# amp_test_arm.net
KiCad netlist of a schematic drawn in EAGLE
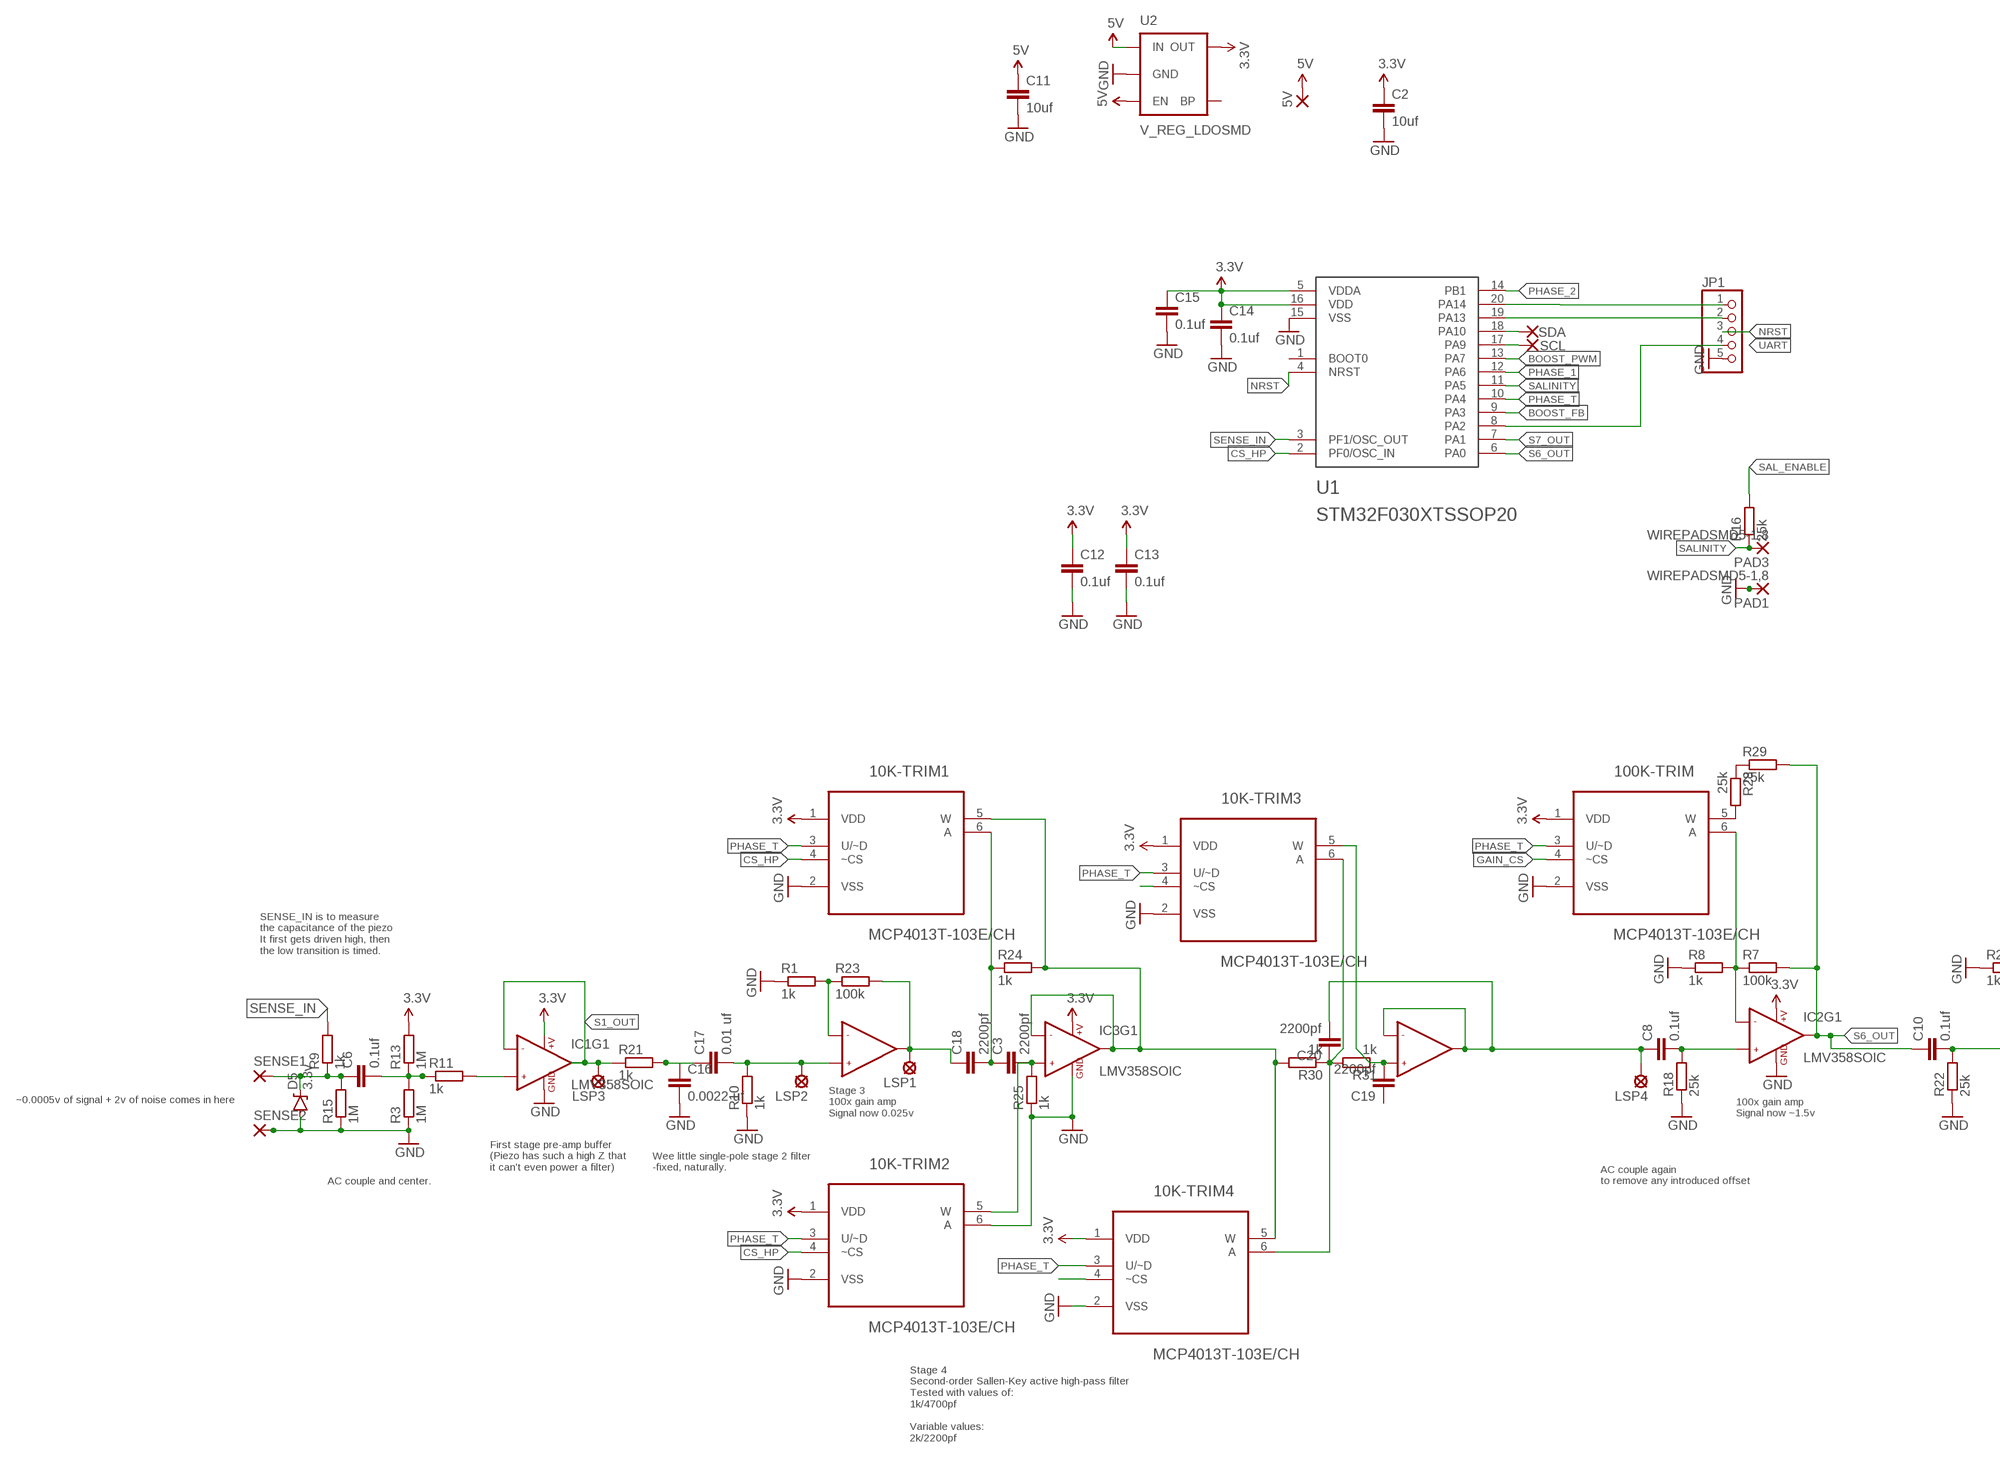
[diagram p0: schematic, sheet 1, part 1 of 2]
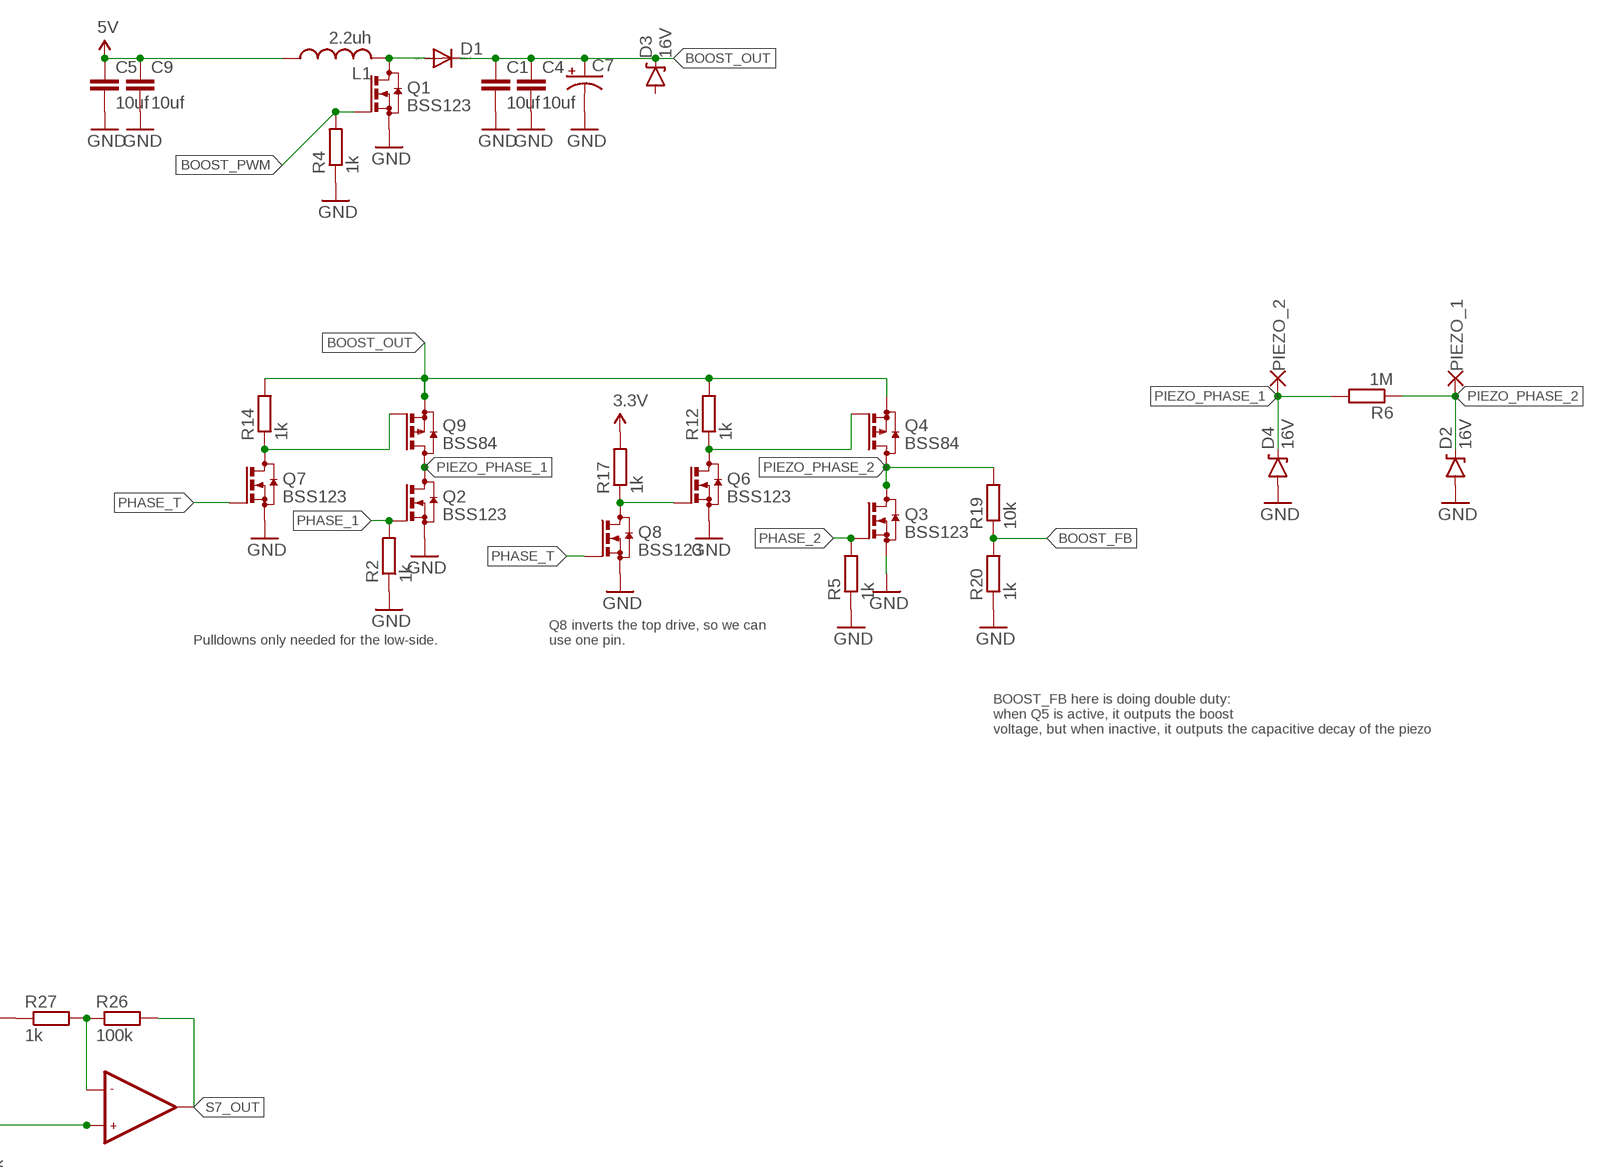
[diagram p1: schematic, sheet 1, part 2 of 2]

(export (version "E")
  (design (tool "Eeschema 10.0.6"))
  (components
    (comp (ref "5V")
      (value "SMD5")
      (footprint "eagle-import:SMD2,54-5,08")
      (libsource (lib "eagle-import") (part "SMD5"))
    )
    (comp (ref "10K-TRIM1")
      (value "MCP4013T-103E/CH")
      (footprint "eagle-import:SOT95P280X145-6N")
      (fields (field (name "DIGI-KEY_PART_NUMBER") "MCP4013T-103E/CHCT-ND") (field (name "MF") "Microchip"))
      (libsource (lib "eagle-import") (part "MCP4013T-103E/CH"))
    )
    (comp (ref "10K-TRIM2")
      (value "MCP4013T-103E/CH")
      (footprint "eagle-import:SOT95P280X145-6N")
      (fields (field (name "DIGI-KEY_PART_NUMBER") "MCP4013T-103E/CHCT-ND") (field (name "MF") "Microchip"))
      (libsource (lib "eagle-import") (part "MCP4013T-103E/CH"))
    )
    (comp (ref "10K-TRIM3")
      (value "MCP4013T-103E/CH")
      (footprint "eagle-import:SOT95P280X145-6N")
      (fields (field (name "DIGI-KEY_PART_NUMBER") "MCP4013T-103E/CHCT-ND") (field (name "MF") "Microchip"))
      (libsource (lib "eagle-import") (part "MCP4013T-103E/CH"))
    )
    (comp (ref "10K-TRIM4")
      (value "MCP4013T-103E/CH")
      (footprint "eagle-import:SOT95P280X145-6N")
      (fields (field (name "DIGI-KEY_PART_NUMBER") "MCP4013T-103E/CHCT-ND") (field (name "MF") "Microchip"))
      (libsource (lib "eagle-import") (part "MCP4013T-103E/CH"))
    )
    (comp (ref "100K-TRIM")
      (value "MCP4013T-103E/CH")
      (footprint "eagle-import:SOT95P280X145-6N")
      (fields (field (name "DIGI-KEY_PART_NUMBER") "MCP4013T-103E/CHCT-ND") (field (name "MF") "Microchip"))
      (libsource (lib "eagle-import") (part "MCP4013T-103E/CH"))
    )
    (comp (ref "C1")
      (value "10uf")
      (footprint "eagle-import:C0805")
      (libsource (lib "eagle-import") (part "C-EUC0805"))
    )
    (comp (ref "C2")
      (value "10uf")
      (footprint "eagle-import:C0603")
      (libsource (lib "eagle-import") (part "C-EUC0603"))
    )
    (comp (ref "C3")
      (value "2200pf")
      (footprint "eagle-import:C0603")
      (libsource (lib "eagle-import") (part "C-EUC0603"))
    )
    (comp (ref "C4")
      (value "10uf")
      (footprint "eagle-import:C0805")
      (libsource (lib "eagle-import") (part "C-EUC0805"))
    )
    (comp (ref "C5")
      (value "10uf")
      (footprint "eagle-import:C0603")
      (libsource (lib "eagle-import") (part "C-EUC0603"))
    )
    (comp (ref "C6")
      (value "0.1uf")
      (footprint "eagle-import:C0603")
      (libsource (lib "eagle-import") (part "C-EUC0603"))
    )
    (comp (ref "C7")
      (value "CAP_POLPTH1")
      (footprint "eagle-import:CPOL-RADIAL-100UF-25V")
      (libsource (lib "eagle-import") (part "CAP_POLPTH1"))
    )
    (comp (ref "C8")
      (value "0.1uf")
      (footprint "eagle-import:C0603")
      (libsource (lib "eagle-import") (part "C-EUC0603"))
    )
    (comp (ref "C9")
      (value "10uf")
      (footprint "eagle-import:C0603")
      (libsource (lib "eagle-import") (part "C-EUC0603"))
    )
    (comp (ref "C10")
      (value "0.1uf")
      (footprint "eagle-import:C0603")
      (libsource (lib "eagle-import") (part "C-EUC0603"))
    )
    (comp (ref "C11")
      (value "10uf")
      (footprint "eagle-import:C0603")
      (libsource (lib "eagle-import") (part "C-EUC0603"))
    )
    (comp (ref "C12")
      (value "0.1uf")
      (footprint "eagle-import:C0603")
      (libsource (lib "eagle-import") (part "C-EUC0603"))
    )
    (comp (ref "C13")
      (value "0.1uf")
      (footprint "eagle-import:C0603")
      (libsource (lib "eagle-import") (part "C-EUC0603"))
    )
    (comp (ref "C14")
      (value "0.1uf")
      (footprint "eagle-import:C0603")
      (libsource (lib "eagle-import") (part "C-EUC0603"))
    )
    (comp (ref "C15")
      (value "0.1uf")
      (footprint "eagle-import:C0603")
      (libsource (lib "eagle-import") (part "C-EUC0603"))
    )
    (comp (ref "C16")
      (value "0.0022 uf")
      (footprint "eagle-import:C0603")
      (libsource (lib "eagle-import") (part "C-EUC0603"))
    )
    (comp (ref "C17")
      (value "0.01 uf")
      (footprint "eagle-import:C0603")
      (libsource (lib "eagle-import") (part "C-EUC0603"))
    )
    (comp (ref "C18")
      (value "2200pf")
      (footprint "eagle-import:C0603")
      (libsource (lib "eagle-import") (part "C-EUC0603"))
    )
    (comp (ref "C19")
      (value "2200pf")
      (footprint "eagle-import:C0603")
      (libsource (lib "eagle-import") (part "C-EUC0603"))
    )
    (comp (ref "C20")
      (value "2200pf")
      (footprint "eagle-import:C0603")
      (libsource (lib "eagle-import") (part "C-EUC0603"))
    )
    (comp (ref "D1")
      (value "CGRM4001-G")
      (footprint "eagle-import:SOD-123_MINI-SMA")
      (libsource (lib "eagle-import") (part "CGRM400-G1"))
    )
    (comp (ref "D2")
      (value "16V")
      (footprint "eagle-import:SOD-323")
      (libsource (lib "eagle-import") (part "DIODE-ZENER3.3V"))
    )
    (comp (ref "D3")
      (value "16V")
      (footprint "eagle-import:SOD-323")
      (libsource (lib "eagle-import") (part "DIODE-ZENER3.3V"))
    )
    (comp (ref "D4")
      (value "16V")
      (footprint "eagle-import:SOD-323")
      (libsource (lib "eagle-import") (part "DIODE-ZENER3.3V"))
    )
    (comp (ref "D5")
      (value "3.3v")
      (footprint "eagle-import:SOD-323")
      (libsource (lib "eagle-import") (part "DIODE-ZENER3.3V"))
    )
    (comp (ref "IC1")
      (value "LMV358SOIC")
      (footprint "eagle-import:SO08")
      (libsource (lib "eagle-import") (part "LMV358SOIC"))
    )
    (comp (ref "IC2")
      (value "LMV358SOIC")
      (footprint "eagle-import:SO08")
      (libsource (lib "eagle-import") (part "LMV358SOIC"))
    )
    (comp (ref "IC3")
      (value "LMV358SOIC")
      (footprint "eagle-import:SO08")
      (libsource (lib "eagle-import") (part "LMV358SOIC"))
    )
    (comp (ref "JP1")
      (value "PINHD-1X5")
      (footprint "eagle-import:1X05")
      (libsource (lib "eagle-import") (part "PINHD-1X5"))
    )
    (comp (ref "L1")
      (value "2.2uh")
      (footprint "eagle-import:L2825P")
      (libsource (lib "eagle-import") (part "L-USL2825P"))
    )
    (comp (ref "LSP1")
      (value "LSP10")
      (footprint "eagle-import:LSP10")
      (libsource (lib "eagle-import") (part "LSP10"))
    )
    (comp (ref "LSP2")
      (value "LSP10")
      (footprint "eagle-import:LSP10")
      (libsource (lib "eagle-import") (part "LSP10"))
    )
    (comp (ref "LSP3")
      (value "LSP10")
      (footprint "eagle-import:LSP10")
      (libsource (lib "eagle-import") (part "LSP10"))
    )
    (comp (ref "LSP4")
      (value "LSP10")
      (footprint "eagle-import:LSP10")
      (libsource (lib "eagle-import") (part "LSP10"))
    )
    (comp (ref "PAD1")
      (value "WIREPADSMD5-1,8")
      (footprint "eagle-import:5-1,8")
      (libsource (lib "eagle-import") (part "WIREPADSMD5-1,8"))
    )
    (comp (ref "PAD3")
      (value "WIREPADSMD5-1,8")
      (footprint "eagle-import:5-1,8")
      (libsource (lib "eagle-import") (part "WIREPADSMD5-1,8"))
    )
    (comp (ref "PIEZO_1")
      (value "SMD5")
      (footprint "eagle-import:SMD2,54-5,08")
      (libsource (lib "eagle-import") (part "SMD5"))
    )
    (comp (ref "PIEZO_2")
      (value "SMD5")
      (footprint "eagle-import:SMD2,54-5,08")
      (libsource (lib "eagle-import") (part "SMD5"))
    )
    (comp (ref "Q1")
      (value "BSS123")
      (footprint "eagle-import:SOT23")
      (libsource (lib "eagle-import") (part "BSS123"))
    )
    (comp (ref "Q2")
      (value "BSS123")
      (footprint "eagle-import:SOT23")
      (libsource (lib "eagle-import") (part "BSS123"))
    )
    (comp (ref "Q3")
      (value "BSS123")
      (footprint "eagle-import:SOT23")
      (libsource (lib "eagle-import") (part "BSS123"))
    )
    (comp (ref "Q4")
      (value "BSS84")
      (footprint "eagle-import:SOT23")
      (libsource (lib "eagle-import") (part "BSS84"))
    )
    (comp (ref "Q6")
      (value "BSS123")
      (footprint "eagle-import:SOT23")
      (libsource (lib "eagle-import") (part "BSS123"))
    )
    (comp (ref "Q7")
      (value "BSS123")
      (footprint "eagle-import:SOT23")
      (libsource (lib "eagle-import") (part "BSS123"))
    )
    (comp (ref "Q8")
      (value "BSS123")
      (footprint "eagle-import:SOT23")
      (libsource (lib "eagle-import") (part "BSS123"))
    )
    (comp (ref "Q9")
      (value "BSS84")
      (footprint "eagle-import:SOT23")
      (libsource (lib "eagle-import") (part "BSS84"))
    )
    (comp (ref "R1")
      (value "1k")
      (footprint "eagle-import:R0603")
      (libsource (lib "eagle-import") (part "R-EU_R0603"))
    )
    (comp (ref "R2")
      (value "1k")
      (footprint "eagle-import:R0603")
      (libsource (lib "eagle-import") (part "R-EU_R0603"))
    )
    (comp (ref "R3")
      (value "1M")
      (footprint "eagle-import:R0603")
      (libsource (lib "eagle-import") (part "R-EU_R0603"))
    )
    (comp (ref "R4")
      (value "1k")
      (footprint "eagle-import:R0603")
      (libsource (lib "eagle-import") (part "R-EU_R0603"))
    )
    (comp (ref "R5")
      (value "1k")
      (footprint "eagle-import:R0603")
      (libsource (lib "eagle-import") (part "R-EU_R0603"))
    )
    (comp (ref "R6")
      (value "1M")
      (footprint "eagle-import:R0603")
      (libsource (lib "eagle-import") (part "R-EU_R0603"))
    )
    (comp (ref "R7")
      (value "100k")
      (footprint "eagle-import:R0603")
      (libsource (lib "eagle-import") (part "R-EU_R0603"))
    )
    (comp (ref "R8")
      (value "1k")
      (footprint "eagle-import:R0603")
      (libsource (lib "eagle-import") (part "R-EU_R0603"))
    )
    (comp (ref "R9")
      (value "1k")
      (footprint "eagle-import:R0603")
      (libsource (lib "eagle-import") (part "R-EU_R0603"))
    )
    (comp (ref "R10")
      (value "1k")
      (footprint "eagle-import:R0603")
      (libsource (lib "eagle-import") (part "R-EU_R0603"))
    )
    (comp (ref "R11")
      (value "1k")
      (footprint "eagle-import:R0603")
      (libsource (lib "eagle-import") (part "R-EU_R0603"))
    )
    (comp (ref "R12")
      (value "1k")
      (footprint "eagle-import:R0603")
      (libsource (lib "eagle-import") (part "R-EU_R0603"))
    )
    (comp (ref "R13")
      (value "1M")
      (footprint "eagle-import:R0603")
      (libsource (lib "eagle-import") (part "R-EU_R0603"))
    )
    (comp (ref "R14")
      (value "1k")
      (footprint "eagle-import:R0603")
      (libsource (lib "eagle-import") (part "R-EU_R0603"))
    )
    (comp (ref "R15")
      (value "1M")
      (footprint "eagle-import:R0603")
      (libsource (lib "eagle-import") (part "R-EU_R0603"))
    )
    (comp (ref "R16")
      (value "25k")
      (footprint "eagle-import:R0603")
      (libsource (lib "eagle-import") (part "R-EU_R0603"))
    )
    (comp (ref "R17")
      (value "1k")
      (footprint "eagle-import:R0603")
      (libsource (lib "eagle-import") (part "R-EU_R0603"))
    )
    (comp (ref "R18")
      (value "25k")
      (footprint "eagle-import:R0603")
      (libsource (lib "eagle-import") (part "R-EU_R0603"))
    )
    (comp (ref "R19")
      (value "10k")
      (footprint "eagle-import:R0603")
      (libsource (lib "eagle-import") (part "R-EU_R0603"))
    )
    (comp (ref "R20")
      (value "1k")
      (footprint "eagle-import:R0603")
      (libsource (lib "eagle-import") (part "R-EU_R0603"))
    )
    (comp (ref "R21")
      (value "1k")
      (footprint "eagle-import:R0603")
      (libsource (lib "eagle-import") (part "R-EU_R0603"))
    )
    (comp (ref "R22")
      (value "25k")
      (footprint "eagle-import:R0603")
      (libsource (lib "eagle-import") (part "R-EU_R0603"))
    )
    (comp (ref "R23")
      (value "100k")
      (footprint "eagle-import:R0603")
      (libsource (lib "eagle-import") (part "R-EU_R0603"))
    )
    (comp (ref "R24")
      (value "1k")
      (footprint "eagle-import:R0603")
      (libsource (lib "eagle-import") (part "R-EU_R0603"))
    )
    (comp (ref "R25")
      (value "1k")
      (footprint "eagle-import:R0603")
      (libsource (lib "eagle-import") (part "R-EU_R0603"))
    )
    (comp (ref "R26")
      (value "100k")
      (footprint "eagle-import:R0603")
      (libsource (lib "eagle-import") (part "R-EU_R0603"))
    )
    (comp (ref "R27")
      (value "1k")
      (footprint "eagle-import:R0603")
      (libsource (lib "eagle-import") (part "R-EU_R0603"))
    )
    (comp (ref "R28")
      (value "25k")
      (footprint "eagle-import:R0603")
      (libsource (lib "eagle-import") (part "R-EU_R0603"))
    )
    (comp (ref "R29")
      (value "25k")
      (footprint "eagle-import:R0603")
      (libsource (lib "eagle-import") (part "R-EU_R0603"))
    )
    (comp (ref "R30")
      (value "1k")
      (footprint "eagle-import:R0603")
      (libsource (lib "eagle-import") (part "R-EU_R0603"))
    )
    (comp (ref "R31")
      (value "1k")
      (footprint "eagle-import:R0603")
      (libsource (lib "eagle-import") (part "R-EU_R0603"))
    )
    (comp (ref "SCL")
      (value "SMD5")
      (footprint "eagle-import:SMD2,54-5,08")
      (libsource (lib "eagle-import") (part "SMD5"))
    )
    (comp (ref "SDA")
      (value "SMD5")
      (footprint "eagle-import:SMD2,54-5,08")
      (libsource (lib "eagle-import") (part "SMD5"))
    )
    (comp (ref "SENSE1")
      (value "SMD5")
      (footprint "eagle-import:SMD2,54-5,08")
      (libsource (lib "eagle-import") (part "SMD5"))
    )
    (comp (ref "SENSE2")
      (value "SMD5")
      (footprint "eagle-import:SMD2,54-5,08")
      (libsource (lib "eagle-import") (part "SMD5"))
    )
    (comp (ref "U1")
      (value "STM32F030XTSSOP20")
      (footprint "eagle-import:TSSOP-20")
      (libsource (lib "eagle-import") (part "STM32F030XTSSOP20"))
    )
    (comp (ref "U2")
      (value "V_REG_LDOSMD")
      (footprint "eagle-import:SOT23-5")
      (libsource (lib "eagle-import") (part "V_REG_LDOSMD"))
    )
  )
  (nets
    (net (code "1") (name "3.3V") (class "Default")
      (node (ref "100K-TRIM") (pin "1") (pinfunction "VDD_1") (pintype "power_in"))
      (node (ref "10K-TRIM1") (pin "1") (pinfunction "VDD_1") (pintype "power_in"))
      (node (ref "10K-TRIM2") (pin "1") (pinfunction "VDD_1") (pintype "power_in"))
      (node (ref "10K-TRIM3") (pin "1") (pinfunction "VDD_1") (pintype "power_in"))
      (node (ref "10K-TRIM4") (pin "1") (pinfunction "VDD_1") (pintype "power_in"))
      (node (ref "C12") (pin "1") (pinfunction "1_1") (pintype "passive"))
      (node (ref "C13") (pin "1") (pinfunction "1_1") (pintype "passive"))
      (node (ref "C14") (pin "1") (pinfunction "1_1") (pintype "passive"))
      (node (ref "C15") (pin "1") (pinfunction "1_1") (pintype "passive"))
      (node (ref "C2") (pin "1") (pinfunction "1_1") (pintype "passive"))
      (node (ref "IC1") (pin "8") (pinfunction "+V_8") (pintype "power_in"))
      (node (ref "IC2") (pin "8") (pinfunction "+V_8") (pintype "power_in"))
      (node (ref "IC3") (pin "8") (pinfunction "+V_8") (pintype "power_in"))
      (node (ref "R13") (pin "2") (pinfunction "2_2") (pintype "passive"))
      (node (ref "R17") (pin "2") (pinfunction "2_2") (pintype "passive"))
      (node (ref "U1") (pin "16") (pinfunction "VDD_16") (pintype "bidirectional"))
      (node (ref "U1") (pin "5") (pinfunction "VDDA_5") (pintype "bidirectional"))
      (node (ref "U2") (pin "5") (pinfunction "OUT_5") (pintype "passive"))
    )
    (net (code "2") (name "5V") (class "Default")
      (node (ref "5V") (pin "1") (pinfunction "P_1") (pintype "passive"))
      (node (ref "C11") (pin "1") (pinfunction "1_1") (pintype "passive"))
      (node (ref "C5") (pin "1") (pinfunction "1_1") (pintype "passive"))
      (node (ref "C9") (pin "1") (pinfunction "1_1") (pintype "passive"))
      (node (ref "L1") (pin "1") (pinfunction "1_1") (pintype "passive"))
      (node (ref "U2") (pin "1") (pinfunction "IN_1") (pintype "input"))
      (node (ref "U2") (pin "3") (pinfunction "EN_3") (pintype "input"))
    )
    (net (code "3") (name "BOOST_FB") (class "Default")
      (node (ref "R19") (pin "1") (pinfunction "1_1") (pintype "passive"))
      (node (ref "R20") (pin "2") (pinfunction "2_2") (pintype "passive"))
      (node (ref "U1") (pin "9") (pinfunction "PA3_9") (pintype "bidirectional"))
    )
    (net (code "4") (name "BOOST_OUT") (class "Default")
      (node (ref "C1") (pin "1") (pinfunction "1_1") (pintype "passive"))
      (node (ref "C4") (pin "1") (pinfunction "1_1") (pintype "passive"))
      (node (ref "C7") (pin "1") (pinfunction "+_1") (pintype "passive"))
      (node (ref "D1") (pin "C") (pinfunction "C_C") (pintype "passive"))
      (node (ref "D3") (pin "C") (pinfunction "C_C") (pintype "passive"))
      (node (ref "Q4") (pin "2") (pinfunction "S_2") (pintype "passive"))
      (node (ref "Q9") (pin "2") (pinfunction "S_2") (pintype "passive"))
      (node (ref "R12") (pin "2") (pinfunction "2_2") (pintype "passive"))
      (node (ref "R14") (pin "2") (pinfunction "2_2") (pintype "passive"))
    )
    (net (code "5") (name "BOOST_PWM") (class "Default")
      (node (ref "Q1") (pin "1") (pinfunction "G_1") (pintype "passive"))
      (node (ref "R4") (pin "2") (pinfunction "2_2") (pintype "passive"))
      (node (ref "U1") (pin "13") (pinfunction "PA7_13") (pintype "bidirectional"))
    )
    (net (code "6") (name "CS_HP") (class "Default")
      (node (ref "10K-TRIM1") (pin "4") (pinfunction "~{CS}_4") (pintype "input"))
      (node (ref "10K-TRIM2") (pin "4") (pinfunction "~{CS}_4") (pintype "input"))
      (node (ref "U1") (pin "2") (pinfunction "PF0/OSC_IN_2") (pintype "bidirectional"))
    )
    (net (code "7") (name "GAIN_CS") (class "Default")
      (node (ref "100K-TRIM") (pin "4") (pinfunction "~{CS}_4") (pintype "input"))
    )
    (net (code "8") (name "GND") (class "Default")
      (node (ref "100K-TRIM") (pin "2") (pinfunction "VSS_2") (pintype "power_in"))
      (node (ref "10K-TRIM1") (pin "2") (pinfunction "VSS_2") (pintype "power_in"))
      (node (ref "10K-TRIM2") (pin "2") (pinfunction "VSS_2") (pintype "power_in"))
      (node (ref "10K-TRIM2") (pin "6") (pinfunction "A_6") (pintype "passive"))
      (node (ref "10K-TRIM3") (pin "2") (pinfunction "VSS_2") (pintype "power_in"))
      (node (ref "10K-TRIM4") (pin "2") (pinfunction "VSS_2") (pintype "power_in"))
      (node (ref "C1") (pin "2") (pinfunction "2_2") (pintype "passive"))
      (node (ref "C11") (pin "2") (pinfunction "2_2") (pintype "passive"))
      (node (ref "C12") (pin "2") (pinfunction "2_2") (pintype "passive"))
      (node (ref "C13") (pin "2") (pinfunction "2_2") (pintype "passive"))
      (node (ref "C14") (pin "2") (pinfunction "2_2") (pintype "passive"))
      (node (ref "C15") (pin "2") (pinfunction "2_2") (pintype "passive"))
      (node (ref "C16") (pin "2") (pinfunction "2_2") (pintype "passive"))
      (node (ref "C2") (pin "2") (pinfunction "2_2") (pintype "passive"))
      (node (ref "C4") (pin "2") (pinfunction "2_2") (pintype "passive"))
      (node (ref "C5") (pin "2") (pinfunction "2_2") (pintype "passive"))
      (node (ref "C7") (pin "2") (pinfunction "-_2") (pintype "passive"))
      (node (ref "C9") (pin "2") (pinfunction "2_2") (pintype "passive"))
      (node (ref "D2") (pin "A") (pinfunction "A_A") (pintype "passive"))
      (node (ref "D4") (pin "A") (pinfunction "A_A") (pintype "passive"))
      (node (ref "D5") (pin "A") (pinfunction "A_A") (pintype "passive"))
      (node (ref "IC1") (pin "4") (pinfunction "GND_4") (pintype "power_in"))
      (node (ref "IC2") (pin "4") (pinfunction "GND_4") (pintype "power_in"))
      (node (ref "IC3") (pin "4") (pinfunction "GND_4") (pintype "power_in"))
      (node (ref "JP1") (pin "5") (pinfunction "5_5") (pintype "passive"))
      (node (ref "PAD1") (pin "1") (pinfunction "P_1") (pintype "passive"))
      (node (ref "Q1") (pin "2") (pinfunction "S_2") (pintype "passive"))
      (node (ref "Q2") (pin "2") (pinfunction "S_2") (pintype "passive"))
      (node (ref "Q3") (pin "2") (pinfunction "S_2") (pintype "passive"))
      (node (ref "Q6") (pin "2") (pinfunction "S_2") (pintype "passive"))
      (node (ref "Q7") (pin "2") (pinfunction "S_2") (pintype "passive"))
      (node (ref "Q8") (pin "2") (pinfunction "S_2") (pintype "passive"))
      (node (ref "R1") (pin "1") (pinfunction "1_1") (pintype "passive"))
      (node (ref "R10") (pin "1") (pinfunction "1_1") (pintype "passive"))
      (node (ref "R15") (pin "1") (pinfunction "1_1") (pintype "passive"))
      (node (ref "R18") (pin "1") (pinfunction "1_1") (pintype "passive"))
      (node (ref "R2") (pin "1") (pinfunction "1_1") (pintype "passive"))
      (node (ref "R20") (pin "1") (pinfunction "1_1") (pintype "passive"))
      (node (ref "R22") (pin "1") (pinfunction "1_1") (pintype "passive"))
      (node (ref "R25") (pin "1") (pinfunction "1_1") (pintype "passive"))
      (node (ref "R27") (pin "1") (pinfunction "1_1") (pintype "passive"))
      (node (ref "R3") (pin "1") (pinfunction "1_1") (pintype "passive"))
      (node (ref "R4") (pin "1") (pinfunction "1_1") (pintype "passive"))
      (node (ref "R5") (pin "1") (pinfunction "1_1") (pintype "passive"))
      (node (ref "R8") (pin "1") (pinfunction "1_1") (pintype "passive"))
      (node (ref "SENSE2") (pin "1") (pinfunction "P_1") (pintype "passive"))
      (node (ref "U1") (pin "15") (pinfunction "VSS_15") (pintype "bidirectional"))
      (node (ref "U2") (pin "2") (pinfunction "GND_2") (pintype "input"))
    )
    (net (code "9") (name "NRST") (class "Default")
      (node (ref "JP1") (pin "3") (pinfunction "3_3") (pintype "passive"))
      (node (ref "U1") (pin "4") (pinfunction "NRST_4") (pintype "bidirectional"))
    )
    (net (code "10") (name "Net-(10K-TRIM1-A)") (class "Default")
      (node (ref "10K-TRIM1") (pin "6") (pinfunction "A_6") (pintype "passive"))
      (node (ref "C18") (pin "2") (pinfunction "2_2") (pintype "passive"))
      (node (ref "C3") (pin "1") (pinfunction "1_1") (pintype "passive"))
      (node (ref "R24") (pin "1") (pinfunction "1_1") (pintype "passive"))
    )
    (net (code "11") (name "Net-(10K-TRIM1-W)") (class "Default")
      (node (ref "10K-TRIM1") (pin "5") (pinfunction "W_5") (pintype "passive"))
      (node (ref "10K-TRIM4") (pin "5") (pinfunction "W_5") (pintype "passive"))
      (node (ref "IC3") (pin "1") (pinfunction "OUT1_1") (pintype "output"))
      (node (ref "IC3") (pin "2") (pinfunction "-IN1_2") (pintype "input"))
      (node (ref "R24") (pin "2") (pinfunction "2_2") (pintype "passive"))
      (node (ref "R30") (pin "2") (pinfunction "2_2") (pintype "passive"))
    )
    (net (code "12") (name "Net-(10K-TRIM2-W)") (class "Default")
      (node (ref "10K-TRIM2") (pin "5") (pinfunction "W_5") (pintype "passive"))
      (node (ref "C3") (pin "2") (pinfunction "2_2") (pintype "passive"))
      (node (ref "IC3") (pin "3") (pinfunction "+IN1_3") (pintype "input"))
      (node (ref "R25") (pin "2") (pinfunction "2_2") (pintype "passive"))
    )
    (net (code "13") (name "Net-(10K-TRIM3-A)") (class "Default")
      (node (ref "10K-TRIM3") (pin "6") (pinfunction "A_6") (pintype "passive"))
      (node (ref "10K-TRIM4") (pin "6") (pinfunction "A_6") (pintype "passive"))
      (node (ref "C20") (pin "1") (pinfunction "1_1") (pintype "passive"))
      (node (ref "R30") (pin "1") (pinfunction "1_1") (pintype "passive"))
      (node (ref "R31") (pin "2") (pinfunction "2_2") (pintype "passive"))
    )
    (net (code "14") (name "Net-(10K-TRIM3-W)") (class "Default")
      (node (ref "10K-TRIM3") (pin "5") (pinfunction "W_5") (pintype "passive"))
      (node (ref "C19") (pin "2") (pinfunction "2_2") (pintype "passive"))
      (node (ref "IC3") (pin "5") (pinfunction "+IN2_5") (pintype "input"))
      (node (ref "R31") (pin "1") (pinfunction "1_1") (pintype "passive"))
    )
    (net (code "15") (name "Net-(100K-TRIM-A)") (class "Default")
      (node (ref "100K-TRIM") (pin "6") (pinfunction "A_6") (pintype "passive"))
      (node (ref "IC2") (pin "2") (pinfunction "-IN1_2") (pintype "input"))
      (node (ref "R7") (pin "1") (pinfunction "1_1") (pintype "passive"))
      (node (ref "R8") (pin "2") (pinfunction "2_2") (pintype "passive"))
    )
    (net (code "16") (name "Net-(100K-TRIM-W)") (class "Default")
      (node (ref "100K-TRIM") (pin "5") (pinfunction "W_5") (pintype "passive"))
      (node (ref "R28") (pin "2") (pinfunction "2_2") (pintype "passive"))
    )
    (net (code "17") (name "Net-(C6-Pad2)") (class "Default")
      (node (ref "C6") (pin "2") (pinfunction "2_2") (pintype "passive"))
      (node (ref "R11") (pin "1") (pinfunction "1_1") (pintype "passive"))
      (node (ref "R13") (pin "1") (pinfunction "1_1") (pintype "passive"))
      (node (ref "R3") (pin "2") (pinfunction "2_2") (pintype "passive"))
    )
    (net (code "18") (name "Net-(C16-Pad1)") (class "Default")
      (node (ref "C16") (pin "1") (pinfunction "1_1") (pintype "passive"))
      (node (ref "C17") (pin "1") (pinfunction "1_1") (pintype "passive"))
      (node (ref "R21") (pin "2") (pinfunction "2_2") (pintype "passive"))
    )
    (net (code "19") (name "Net-(IC1A-+IN1)") (class "Default")
      (node (ref "IC1") (pin "3") (pinfunction "+IN1_3") (pintype "input"))
      (node (ref "R11") (pin "2") (pinfunction "2_2") (pintype "passive"))
    )
    (net (code "20") (name "Net-(IC1B-+IN2)") (class "Default")
      (node (ref "C17") (pin "2") (pinfunction "2_2") (pintype "passive"))
      (node (ref "IC1") (pin "5") (pinfunction "+IN2_5") (pintype "input"))
      (node (ref "LSP2") (pin "MP") (pinfunction "MP_MP") (pintype "passive"))
      (node (ref "R10") (pin "2") (pinfunction "2_2") (pintype "passive"))
    )
    (net (code "21") (name "Net-(IC1B--IN2)") (class "Default")
      (node (ref "IC1") (pin "6") (pinfunction "-IN2_6") (pintype "input"))
      (node (ref "R1") (pin "2") (pinfunction "2_2") (pintype "passive"))
      (node (ref "R23") (pin "1") (pinfunction "1_1") (pintype "passive"))
    )
    (net (code "22") (name "Net-(IC1B-OUT2)") (class "Default")
      (node (ref "C18") (pin "1") (pinfunction "1_1") (pintype "passive"))
      (node (ref "IC1") (pin "7") (pinfunction "OUT2_7") (pintype "output"))
      (node (ref "LSP1") (pin "MP") (pinfunction "MP_MP") (pintype "passive"))
      (node (ref "R23") (pin "2") (pinfunction "2_2") (pintype "passive"))
    )
    (net (code "23") (name "Net-(IC2A-+IN1)") (class "Default")
      (node (ref "C8") (pin "2") (pinfunction "2_2") (pintype "passive"))
      (node (ref "IC2") (pin "3") (pinfunction "+IN1_3") (pintype "input"))
      (node (ref "R18") (pin "2") (pinfunction "2_2") (pintype "passive"))
    )
    (net (code "24") (name "Net-(IC2B-+IN2)") (class "Default")
      (node (ref "C10") (pin "2") (pinfunction "2_2") (pintype "passive"))
      (node (ref "IC2") (pin "5") (pinfunction "+IN2_5") (pintype "input"))
      (node (ref "R22") (pin "2") (pinfunction "2_2") (pintype "passive"))
    )
    (net (code "25") (name "Net-(IC2B--IN2)") (class "Default")
      (node (ref "IC2") (pin "6") (pinfunction "-IN2_6") (pintype "input"))
      (node (ref "R26") (pin "1") (pinfunction "1_1") (pintype "passive"))
      (node (ref "R27") (pin "2") (pinfunction "2_2") (pintype "passive"))
    )
    (net (code "26") (name "Net-(IC3B--IN2)") (class "Default")
      (node (ref "C20") (pin "2") (pinfunction "2_2") (pintype "passive"))
      (node (ref "C8") (pin "1") (pinfunction "1_1") (pintype "passive"))
      (node (ref "IC3") (pin "6") (pinfunction "-IN2_6") (pintype "input"))
      (node (ref "IC3") (pin "7") (pinfunction "OUT2_7") (pintype "output"))
      (node (ref "LSP4") (pin "MP") (pinfunction "MP_MP") (pintype "passive"))
    )
    (net (code "27") (name "Net-(Q1-D)") (class "Default")
      (node (ref "D1") (pin "A") (pinfunction "A_A") (pintype "passive"))
      (node (ref "L1") (pin "2") (pinfunction "2_2") (pintype "passive"))
      (node (ref "Q1") (pin "3") (pinfunction "D_3") (pintype "passive"))
    )
    (net (code "28") (name "Net-(Q4-G)") (class "Default")
      (node (ref "Q4") (pin "1") (pinfunction "G_1") (pintype "passive"))
      (node (ref "Q6") (pin "3") (pinfunction "D_3") (pintype "passive"))
      (node (ref "R12") (pin "1") (pinfunction "1_1") (pintype "passive"))
    )
    (net (code "29") (name "Net-(Q6-G)") (class "Default")
      (node (ref "Q6") (pin "1") (pinfunction "G_1") (pintype "passive"))
      (node (ref "Q8") (pin "3") (pinfunction "D_3") (pintype "passive"))
      (node (ref "R17") (pin "1") (pinfunction "1_1") (pintype "passive"))
    )
    (net (code "30") (name "Net-(Q7-D)") (class "Default")
      (node (ref "Q7") (pin "3") (pinfunction "D_3") (pintype "passive"))
      (node (ref "Q9") (pin "1") (pinfunction "G_1") (pintype "passive"))
      (node (ref "R14") (pin "1") (pinfunction "1_1") (pintype "passive"))
    )
    (net (code "31") (name "Net-(R28-Pad1)") (class "Default")
      (node (ref "R28") (pin "1") (pinfunction "1_1") (pintype "passive"))
      (node (ref "R29") (pin "1") (pinfunction "1_1") (pintype "passive"))
    )
    (net (code "32") (name "Net-(SCL-P)") (class "Default")
      (node (ref "SCL") (pin "1") (pinfunction "P_1") (pintype "passive"))
      (node (ref "U1") (pin "17") (pinfunction "PA9_17") (pintype "bidirectional"))
    )
    (net (code "33") (name "Net-(SDA-P)") (class "Default")
      (node (ref "SDA") (pin "1") (pinfunction "P_1") (pintype "passive"))
      (node (ref "U1") (pin "18") (pinfunction "PA10_18") (pintype "bidirectional"))
    )
    (net (code "34") (name "Net-(U1-PA13)") (class "Default")
      (node (ref "JP1") (pin "2") (pinfunction "2_2") (pintype "passive"))
      (node (ref "U1") (pin "19") (pinfunction "PA13_19") (pintype "bidirectional"))
    )
    (net (code "35") (name "Net-(U1-PA14)") (class "Default")
      (node (ref "JP1") (pin "1") (pinfunction "1_1") (pintype "passive"))
      (node (ref "U1") (pin "20") (pinfunction "PA14_20") (pintype "bidirectional"))
    )
    (net (code "36") (name "PHASE_1") (class "Default")
      (node (ref "Q2") (pin "1") (pinfunction "G_1") (pintype "passive"))
      (node (ref "R2") (pin "2") (pinfunction "2_2") (pintype "passive"))
      (node (ref "U1") (pin "12") (pinfunction "PA6_12") (pintype "bidirectional"))
    )
    (net (code "37") (name "PHASE_2") (class "Default")
      (node (ref "Q3") (pin "1") (pinfunction "G_1") (pintype "passive"))
      (node (ref "R5") (pin "2") (pinfunction "2_2") (pintype "passive"))
      (node (ref "U1") (pin "14") (pinfunction "PB1_14") (pintype "bidirectional"))
    )
    (net (code "38") (name "PHASE_T") (class "Default")
      (node (ref "100K-TRIM") (pin "3") (pinfunction "U/~{D}_3") (pintype "input"))
      (node (ref "10K-TRIM1") (pin "3") (pinfunction "U/~{D}_3") (pintype "input"))
      (node (ref "10K-TRIM2") (pin "3") (pinfunction "U/~{D}_3") (pintype "input"))
      (node (ref "10K-TRIM3") (pin "3") (pinfunction "U/~{D}_3") (pintype "input"))
      (node (ref "10K-TRIM4") (pin "3") (pinfunction "U/~{D}_3") (pintype "input"))
      (node (ref "Q7") (pin "1") (pinfunction "G_1") (pintype "passive"))
      (node (ref "Q8") (pin "1") (pinfunction "G_1") (pintype "passive"))
      (node (ref "U1") (pin "10") (pinfunction "PA4_10") (pintype "bidirectional"))
    )
    (net (code "39") (name "PIEZO_PHASE_1") (class "Default")
      (node (ref "D4") (pin "C") (pinfunction "C_C") (pintype "passive"))
      (node (ref "PIEZO_2") (pin "1") (pinfunction "P_1") (pintype "passive"))
      (node (ref "Q2") (pin "3") (pinfunction "D_3") (pintype "passive"))
      (node (ref "Q9") (pin "3") (pinfunction "D_3") (pintype "passive"))
      (node (ref "R6") (pin "2") (pinfunction "2_2") (pintype "passive"))
    )
    (net (code "40") (name "PIEZO_PHASE_2") (class "Default")
      (node (ref "D2") (pin "C") (pinfunction "C_C") (pintype "passive"))
      (node (ref "PIEZO_1") (pin "1") (pinfunction "P_1") (pintype "passive"))
      (node (ref "Q3") (pin "3") (pinfunction "D_3") (pintype "passive"))
      (node (ref "Q4") (pin "3") (pinfunction "D_3") (pintype "passive"))
      (node (ref "R19") (pin "2") (pinfunction "2_2") (pintype "passive"))
      (node (ref "R6") (pin "1") (pinfunction "1_1") (pintype "passive"))
    )
    (net (code "41") (name "S1_OUT") (class "Default")
      (node (ref "IC1") (pin "1") (pinfunction "OUT1_1") (pintype "output"))
      (node (ref "IC1") (pin "2") (pinfunction "-IN1_2") (pintype "input"))
      (node (ref "LSP3") (pin "MP") (pinfunction "MP_MP") (pintype "passive"))
      (node (ref "R21") (pin "1") (pinfunction "1_1") (pintype "passive"))
    )
    (net (code "42") (name "S6_OUT") (class "Default")
      (node (ref "C10") (pin "1") (pinfunction "1_1") (pintype "passive"))
      (node (ref "IC2") (pin "1") (pinfunction "OUT1_1") (pintype "output"))
      (node (ref "R29") (pin "2") (pinfunction "2_2") (pintype "passive"))
      (node (ref "R7") (pin "2") (pinfunction "2_2") (pintype "passive"))
      (node (ref "U1") (pin "6") (pinfunction "PA0_6") (pintype "bidirectional"))
    )
    (net (code "43") (name "S7_OUT") (class "Default")
      (node (ref "IC2") (pin "7") (pinfunction "OUT2_7") (pintype "output"))
      (node (ref "R26") (pin "2") (pinfunction "2_2") (pintype "passive"))
      (node (ref "U1") (pin "7") (pinfunction "PA1_7") (pintype "bidirectional"))
    )
    (net (code "44") (name "SALINITY") (class "Default")
      (node (ref "PAD3") (pin "1") (pinfunction "P_1") (pintype "passive"))
      (node (ref "R16") (pin "1") (pinfunction "1_1") (pintype "passive"))
      (node (ref "U1") (pin "11") (pinfunction "PA5_11") (pintype "bidirectional"))
    )
    (net (code "45") (name "SAL_ENABLE") (class "Default")
      (node (ref "R16") (pin "2") (pinfunction "2_2") (pintype "passive"))
    )
    (net (code "46") (name "SENSE_IN") (class "Default")
      (node (ref "C6") (pin "1") (pinfunction "1_1") (pintype "passive"))
      (node (ref "D5") (pin "C") (pinfunction "C_C") (pintype "passive"))
      (node (ref "R15") (pin "2") (pinfunction "2_2") (pintype "passive"))
      (node (ref "R9") (pin "1") (pinfunction "1_1") (pintype "passive"))
      (node (ref "R9") (pin "2") (pinfunction "2_2") (pintype "passive"))
      (node (ref "SENSE1") (pin "1") (pinfunction "P_1") (pintype "passive"))
      (node (ref "U1") (pin "3") (pinfunction "PF1/OSC_OUT_3") (pintype "bidirectional"))
    )
    (net (code "47") (name "UART") (class "Default")
      (node (ref "JP1") (pin "4") (pinfunction "4_4") (pintype "passive"))
      (node (ref "U1") (pin "8") (pinfunction "PA2_8") (pintype "bidirectional"))
    )
    (net (code "48") (name "unconnected-(10K-TRIM3-~{CS}-Pad4)") (class "Default")
      (node (ref "10K-TRIM3") (pin "4") (pinfunction "~{CS}_4") (pintype "input"))
    )
    (net (code "49") (name "unconnected-(10K-TRIM4-~{CS}-Pad4)") (class "Default")
      (node (ref "10K-TRIM4") (pin "4") (pinfunction "~{CS}_4") (pintype "input"))
    )
    (net (code "50") (name "unconnected-(C19-Pad1)") (class "Default")
      (node (ref "C19") (pin "1") (pinfunction "1_1") (pintype "passive"))
    )
    (net (code "51") (name "unconnected-(D3-PadA)") (class "Default")
      (node (ref "D3") (pin "A") (pinfunction "A_A") (pintype "passive"))
    )
    (net (code "52") (name "unconnected-(U1-BOOT0-Pad1)") (class "Default")
      (node (ref "U1") (pin "1") (pinfunction "BOOT0_1") (pintype "bidirectional"))
    )
    (net (code "53") (name "unconnected-(U2-BP-Pad4)") (class "Default")
      (node (ref "U2") (pin "4") (pinfunction "BP_4") (pintype "input"))
    )
  )
)
